# DM2097_Connector_A.net
KiCad netlist of a schematic drawn in Altium Designer
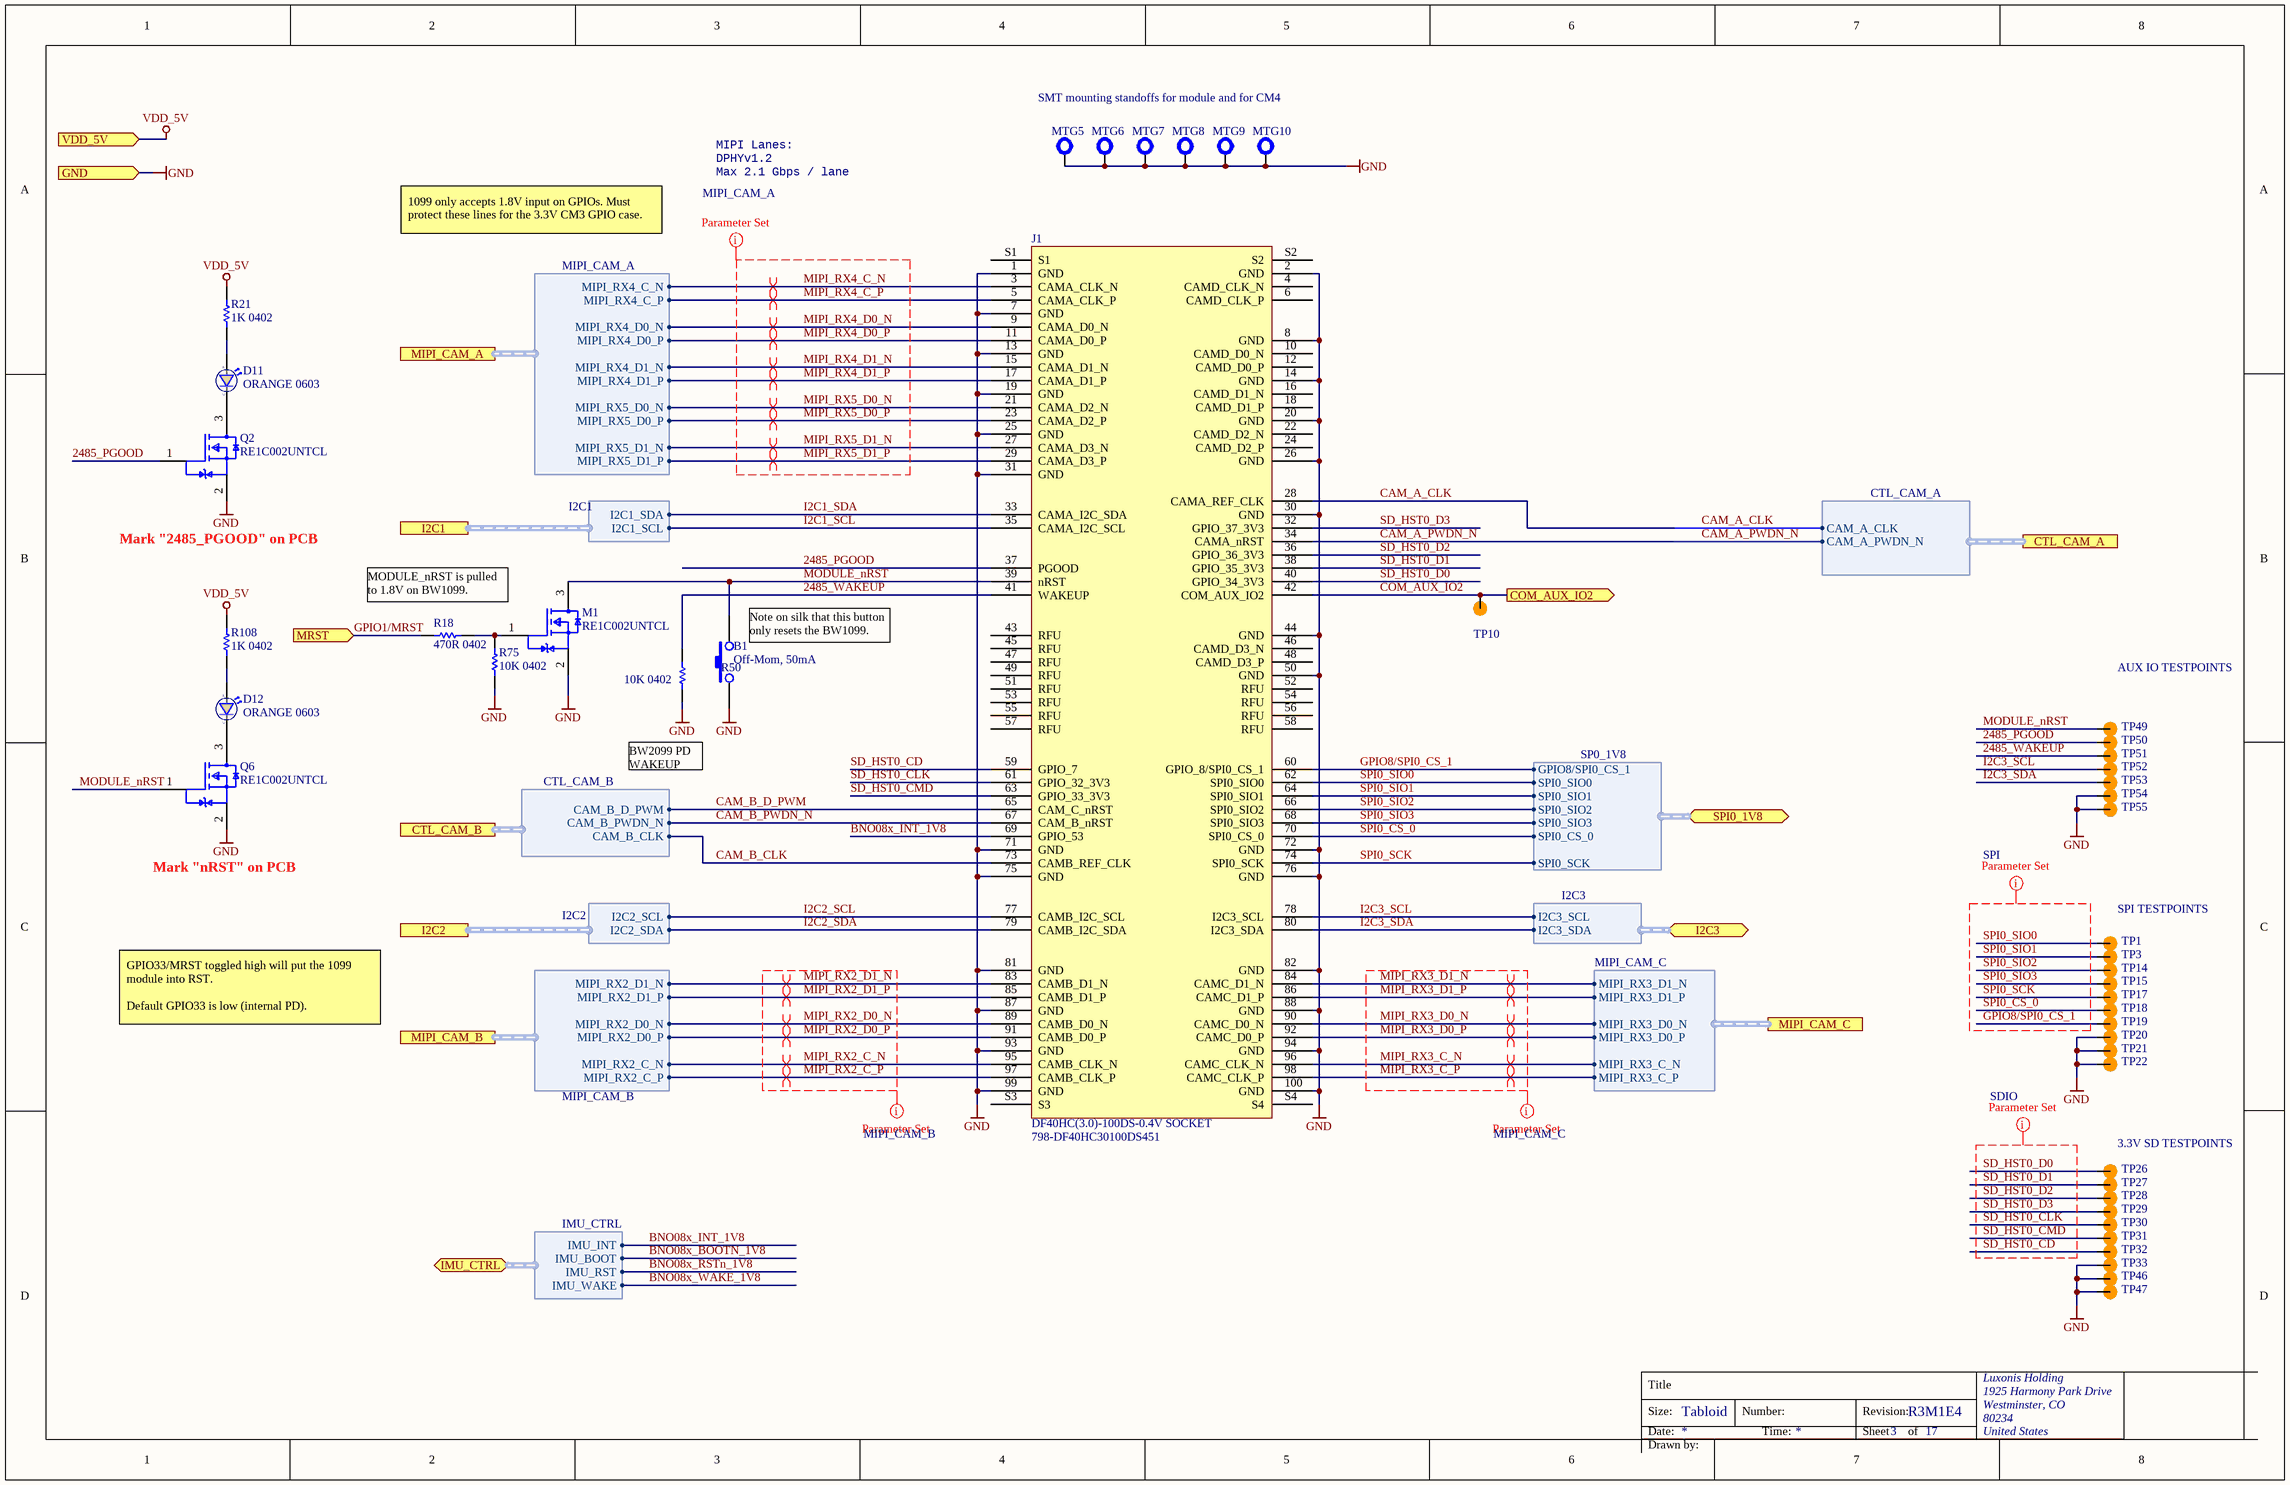
[diagram p0: DM2097_Connector_A.SchDoc]

(export (version "E")
  (design (tool "Eeschema 10.0.6"))
  (components
    (comp (ref "B1")
      (value "Off-Mom, 50mA")
      (footprint "LuxonisMaster:DTSM-32N-V")
      (description "SWITCH TACTILE SMT 3.5mm * 6mm , brown 160gf")
      (libsource (lib "LuxonisMaster") (part "DTSM-32N-V"))
    )
    (comp (ref "D11")
      (value "ORANGE 0603")
      (footprint "LuxonisMaster:SML_D1xx8W")
      (description "LED ORANGE DIFFUSED 0603 SMD Orange 605nm LED Indication - Discrete 2.2V 0603 (1608 Metric)")
      (libsource (lib "LuxonisMaster") (part "SML-D12D8WT86"))
    )
    (comp (ref "D12")
      (value "ORANGE 0603")
      (footprint "LuxonisMaster:SML_D1xx8W")
      (description "LED ORANGE DIFFUSED 0603 SMD Orange 605nm LED Indication - Discrete 2.2V 0603 (1608 Metric)")
      (libsource (lib "LuxonisMaster") (part "SML-D12D8WT86"))
    )
    (comp (ref "J1")
      (value "DF40HC(3.0)-100DS-0.4V SOCKET")
      (footprint "DF40HC-3.0-100DS-0.4V_minpad")
      (description "Conn Board to Board RCP 100 POS 0.4mm Solder ST SMD T/R")
      (fields (field (name "SUPPLIER PART NUMBER 1") "798-DF40HC30100DS451"))
      (libsource (lib "LuxonisMaster_OPAL") (part "BW2099_SCKT_Conn_A"))
    )
    (comp (ref "M1")
      (value "RE1C002UNTCL")
      (footprint "LuxonisMaster:RE1C002UNTCL")
      (description "VISHAY - SI1062X-T1-GE3 - MOSFET Transistor, N Channel, 530 mA, 20 V, 0.35 ohm, 4.5 V, 1 V")
      (libsource (lib "LuxonisMaster") (part "RE1C002UNTCL"))
    )
    (comp (ref "MTG5")
      (value "M2, 3MM steel spacer on M2.5 mounting pad")
      (footprint "9774030943R")
      (description "Spacers/Standoffs")
      (libsource (lib "DM1097_R1M1E1") (part "9774030943R"))
    )
    (comp (ref "MTG6")
      (value "M2, 3MM steel spacer on M2.5 mounting pad")
      (footprint "9774030943R")
      (description "Spacers/Standoffs")
      (libsource (lib "DM1097_R1M1E1") (part "9774030943R"))
    )
    (comp (ref "MTG7")
      (value "M2, 3MM steel spacer on M2.5 mounting pad")
      (footprint "9774030943R")
      (description "Spacers/Standoffs")
      (libsource (lib "DM1097_R1M1E1") (part "9774030943R"))
    )
    (comp (ref "MTG8")
      (value "M2, 3MM steel spacer on M2.5 mounting pad")
      (footprint "9774030943R")
      (description "Spacers/Standoffs")
      (libsource (lib "DM1097_R1M1E1") (part "9774030943R"))
    )
    (comp (ref "MTG9")
      (value "M2, 3MM steel spacer on M2.5 mounting pad")
      (footprint "9774030943R")
      (description "Spacers/Standoffs")
      (libsource (lib "DM1097_R1M1E1") (part "9774030943R"))
    )
    (comp (ref "MTG10")
      (value "M2, 3MM steel spacer on M2.5 mounting pad")
      (footprint "9774030943R")
      (description "Spacers/Standoffs")
      (libsource (lib "DM1097_R1M1E1") (part "9774030943R"))
    )
    (comp (ref "Q2")
      (value "RE1C002UNTCL")
      (footprint "LuxonisMaster:RE1C002UNTCL")
      (description "VISHAY - SI1062X-T1-GE3 - MOSFET Transistor, N Channel, 530 mA, 20 V, 0.35 ohm, 4.5 V, 1 V")
      (libsource (lib "LuxonisMaster") (part "RE1C002UNTCL"))
    )
    (comp (ref "Q6")
      (value "RE1C002UNTCL")
      (footprint "LuxonisMaster:RE1C002UNTCL")
      (description "VISHAY - SI1062X-T1-GE3 - MOSFET Transistor, N Channel, 530 mA, 20 V, 0.35 ohm, 4.5 V, 1 V")
      (libsource (lib "LuxonisMaster") (part "RE1C002UNTCL"))
    )
    (comp (ref "R18")
      (value "470R 0402")
      (footprint "RES_Altium_Vault_Generic:RESC0402(1005)_N")
      (description "RES SMD 470 OHM 1% 1/16W 0402")
      (fields (field (name "TOLERANCE") "1%"))
      (libsource (lib "LuxonisMaster") (part "CRCW0402470RFKED"))
    )
    (comp (ref "R21")
      (value "1K 0402")
      (footprint "RES_Altium_Vault_Generic:RESC0402(1005)_L")
      (fields (field (name "TOLERANCE") "1%"))
      (libsource (lib "LuxonisMaster") (part "RC0402FR-071KL"))
    )
    (comp (ref "R50")
      (value "10K 0402")
      (footprint "RES_Altium_Vault_Generic:RESC0402(1005)_L")
      (fields (field (name "TOLERANCE") "1%"))
      (libsource (lib "LuxonisMaster") (part "RC0402FR-1310KL"))
    )
    (comp (ref "R75")
      (value "10K 0402")
      (footprint "RES_Altium_Vault_Generic:RESC0402(1005)_N")
      (fields (field (name "TOLERANCE") "1%"))
      (libsource (lib "LuxonisMaster") (part "RC0402FR-1310KL"))
    )
    (comp (ref "R108")
      (value "1K 0402")
      (footprint "RES_Altium_Vault_Generic:RESC0402(1005)_L")
      (fields (field (name "TOLERANCE") "1%"))
      (libsource (lib "LuxonisMaster") (part "RC0402FR-071KL"))
    )
    (comp (ref "TP1")
      (value "TP100_200_NS")
      (footprint "LuxonisMaster:TP100_200_NS")
      (libsource (lib "LuxonisMaster") (part "TEST_POINT"))
    )
    (comp (ref "TP3")
      (value "TP100_200_NS")
      (footprint "LuxonisMaster:TP100_200_NS")
      (libsource (lib "LuxonisMaster") (part "TEST_POINT"))
    )
    (comp (ref "TP10")
      (value "TP100_200_NS")
      (footprint "LuxonisMaster:TP100_200_NS")
      (libsource (lib "LuxonisMaster") (part "TEST_POINT"))
    )
    (comp (ref "TP14")
      (value "TP100_200_NS")
      (footprint "LuxonisMaster:TP100_200_NS")
      (libsource (lib "LuxonisMaster") (part "TEST_POINT"))
    )
    (comp (ref "TP15")
      (value "TP100_200_NS")
      (footprint "LuxonisMaster:TP100_200_NS")
      (libsource (lib "LuxonisMaster") (part "TEST_POINT"))
    )
    (comp (ref "TP17")
      (value "TP100_200_NS")
      (footprint "LuxonisMaster:TP100_200_NS")
      (libsource (lib "LuxonisMaster") (part "TEST_POINT"))
    )
    (comp (ref "TP18")
      (value "TP100_200_NS")
      (footprint "LuxonisMaster:TP100_200_NS")
      (libsource (lib "LuxonisMaster") (part "TEST_POINT"))
    )
    (comp (ref "TP19")
      (value "TP100_200_NS")
      (footprint "LuxonisMaster:TP100_200_NS")
      (libsource (lib "LuxonisMaster") (part "TEST_POINT"))
    )
    (comp (ref "TP20")
      (value "TP100_200_NS")
      (footprint "LuxonisMaster:TP100_200_NS")
      (libsource (lib "LuxonisMaster") (part "TEST_POINT"))
    )
    (comp (ref "TP21")
      (value "TP100_200_NS")
      (footprint "LuxonisMaster:TP100_200_NS")
      (libsource (lib "LuxonisMaster") (part "TEST_POINT"))
    )
    (comp (ref "TP22")
      (value "TP100_200_NS")
      (footprint "LuxonisMaster:TP100_200_NS")
      (libsource (lib "LuxonisMaster") (part "TEST_POINT"))
    )
    (comp (ref "TP26")
      (value "TP100_200_NS")
      (footprint "LuxonisMaster:TP100_200_NS")
      (libsource (lib "LuxonisMaster") (part "TEST_POINT"))
    )
    (comp (ref "TP27")
      (value "TP100_200_NS")
      (footprint "LuxonisMaster:TP100_200_NS")
      (libsource (lib "LuxonisMaster") (part "TEST_POINT"))
    )
    (comp (ref "TP28")
      (value "TP100_200_NS")
      (footprint "LuxonisMaster:TP100_200_NS")
      (libsource (lib "LuxonisMaster") (part "TEST_POINT"))
    )
    (comp (ref "TP29")
      (value "TP100_200_NS")
      (footprint "LuxonisMaster:TP100_200_NS")
      (libsource (lib "LuxonisMaster") (part "TEST_POINT"))
    )
    (comp (ref "TP30")
      (value "TP100_200_NS")
      (footprint "LuxonisMaster:TP100_200_NS")
      (libsource (lib "LuxonisMaster") (part "TEST_POINT"))
    )
    (comp (ref "TP31")
      (value "TP100_200_NS")
      (footprint "LuxonisMaster:TP100_200_NS")
      (libsource (lib "LuxonisMaster") (part "TEST_POINT"))
    )
    (comp (ref "TP32")
      (value "TP100_200_NS")
      (footprint "LuxonisMaster:TP100_200_NS")
      (libsource (lib "LuxonisMaster") (part "TEST_POINT"))
    )
    (comp (ref "TP33")
      (value "TP100_200_NS")
      (footprint "LuxonisMaster:TP100_200_NS")
      (libsource (lib "LuxonisMaster") (part "TEST_POINT"))
    )
    (comp (ref "TP46")
      (value "TP100_200_NS")
      (footprint "LuxonisMaster:TP100_200_NS")
      (libsource (lib "LuxonisMaster") (part "TEST_POINT"))
    )
    (comp (ref "TP47")
      (value "TP100_200_NS")
      (footprint "LuxonisMaster:TP100_200_NS")
      (libsource (lib "LuxonisMaster") (part "TEST_POINT"))
    )
    (comp (ref "TP49")
      (value "TP100_200_NS")
      (footprint "LuxonisMaster:TP100_200_NS")
      (libsource (lib "LuxonisMaster") (part "TEST_POINT"))
    )
    (comp (ref "TP50")
      (value "TP100_200_NS")
      (footprint "LuxonisMaster:TP100_200_NS")
      (libsource (lib "LuxonisMaster") (part "TEST_POINT"))
    )
    (comp (ref "TP51")
      (value "TP100_200_NS")
      (footprint "LuxonisMaster:TP100_200_NS")
      (libsource (lib "LuxonisMaster") (part "TEST_POINT"))
    )
    (comp (ref "TP52")
      (value "TP100_200_NS")
      (footprint "LuxonisMaster:TP100_200_NS")
      (libsource (lib "LuxonisMaster") (part "TEST_POINT"))
    )
    (comp (ref "TP53")
      (value "TP100_200_NS")
      (footprint "LuxonisMaster:TP100_200_NS")
      (libsource (lib "LuxonisMaster") (part "TEST_POINT"))
    )
    (comp (ref "TP54")
      (value "TP100_200_NS")
      (footprint "LuxonisMaster:TP100_200_NS")
      (libsource (lib "LuxonisMaster") (part "TEST_POINT"))
    )
    (comp (ref "TP55")
      (value "TP100_200_NS")
      (footprint "LuxonisMaster:TP100_200_NS")
      (libsource (lib "LuxonisMaster") (part "TEST_POINT"))
    )
  )
  (nets
    (net (code "11") (name "/2485_PGOOD") (class "Default")
      (node (ref "J1") (pin "37") (pinfunction "PGOOD_37") (pintype "passive"))
      (node (ref "Q2") (pin "1") (pinfunction "Gate_1") (pintype "passive"))
      (node (ref "TP50") (pin "1") (pintype "passive"))
    )
    (net (code "12") (name "/2485_WAKEUP") (class "Default")
      (node (ref "J1") (pin "41") (pinfunction "WAKEUP_41") (pintype "passive"))
      (node (ref "R50") (pin "2") (pinfunction "2_2") (pintype "passive"))
      (node (ref "TP51") (pin "1") (pintype "passive"))
    )
    (net (code "14") (name "/BNO08x_INT_1V8") (class "Default")
      (node (ref "J1") (pin "69") (pinfunction "GPIO_53_69") (pintype "passive"))
    )
    (net (code "17") (name "/CAM_A_CLK") (class "Default")
      (node (ref "J1") (pin "28") (pinfunction "CAMA_REF_CLK_28") (pintype "passive"))
    )
    (net (code "18") (name "/CAM_A_PWDN_N") (class "Default")
      (node (ref "J1") (pin "34") (pinfunction "CAMA_nRST_34") (pintype "passive"))
    )
    (net (code "19") (name "/CAM_B_CLK") (class "Default")
      (node (ref "J1") (pin "73") (pinfunction "CAMB_REF_CLK_73") (pintype "passive"))
    )
    (net (code "20") (name "/CAM_B_D_PWM") (class "Default")
      (node (ref "J1") (pin "65") (pinfunction "CAM_C_nRST_65") (pintype "passive"))
    )
    (net (code "21") (name "/CAM_B_PWDN_N") (class "Default")
      (node (ref "J1") (pin "67") (pinfunction "CAM_B_nRST_67") (pintype "passive"))
    )
    (net (code "22") (name "/COM_AUX_IO2") (class "Default")
      (node (ref "J1") (pin "42") (pinfunction "COM_AUX_IO2_42") (pintype "passive"))
      (node (ref "TP10") (pin "1") (pintype "passive"))
    )
    (net (code "23") (name "/GPIO1{slash}MRST") (class "Default")
      (node (ref "R18") (pin "1") (pinfunction "1_1") (pintype "passive"))
    )
    (net (code "24") (name "/GPIO8{slash}SPI0_CS_1") (class "Default")
      (node (ref "J1") (pin "60") (pinfunction "GPIO_8/SPI0_CS_1_60") (pintype "passive"))
      (node (ref "TP19") (pin "1") (pintype "passive"))
    )
    (net (code "25") (name "/I2C1_SCL") (class "Default")
      (node (ref "J1") (pin "35") (pinfunction "CAMA_I2C_SCL_35") (pintype "passive"))
    )
    (net (code "26") (name "/I2C1_SDA") (class "Default")
      (node (ref "J1") (pin "33") (pinfunction "CAMA_I2C_SDA_33") (pintype "passive"))
    )
    (net (code "27") (name "/I2C2_SCL") (class "Default")
      (node (ref "J1") (pin "77") (pinfunction "CAMB_I2C_SCL_77") (pintype "passive"))
    )
    (net (code "28") (name "/I2C2_SDA") (class "Default")
      (node (ref "J1") (pin "79") (pinfunction "CAMB_I2C_SDA_79") (pintype "passive"))
    )
    (net (code "29") (name "/I2C3_SCL") (class "Default")
      (node (ref "J1") (pin "78") (pinfunction "I2C3_SCL_78") (pintype "passive"))
      (node (ref "TP52") (pin "1") (pintype "passive"))
    )
    (net (code "30") (name "/I2C3_SDA") (class "Default")
      (node (ref "J1") (pin "80") (pinfunction "I2C3_SDA_80") (pintype "passive"))
      (node (ref "TP53") (pin "1") (pintype "passive"))
    )
    (net (code "31") (name "/MIPI_RX2_C_N") (class "Default")
      (node (ref "J1") (pin "95") (pinfunction "CAMB_CLK_N_95") (pintype "passive"))
    )
    (net (code "32") (name "/MIPI_RX2_C_P") (class "Default")
      (node (ref "J1") (pin "97") (pinfunction "CAMB_CLK_P_97") (pintype "passive"))
    )
    (net (code "33") (name "/MIPI_RX2_D0_N") (class "Default")
      (node (ref "J1") (pin "89") (pinfunction "CAMB_D0_N_89") (pintype "passive"))
    )
    (net (code "34") (name "/MIPI_RX2_D0_P") (class "Default")
      (node (ref "J1") (pin "91") (pinfunction "CAMB_D0_P_91") (pintype "passive"))
    )
    (net (code "35") (name "/MIPI_RX2_D1_N") (class "Default")
      (node (ref "J1") (pin "83") (pinfunction "CAMB_D1_N_83") (pintype "passive"))
    )
    (net (code "36") (name "/MIPI_RX2_D1_P") (class "Default")
      (node (ref "J1") (pin "85") (pinfunction "CAMB_D1_P_85") (pintype "passive"))
    )
    (net (code "37") (name "/MIPI_RX3_C_N") (class "Default")
      (node (ref "J1") (pin "96") (pinfunction "CAMC_CLK_N_96") (pintype "passive"))
    )
    (net (code "38") (name "/MIPI_RX3_C_P") (class "Default")
      (node (ref "J1") (pin "98") (pinfunction "CAMC_CLK_P_98") (pintype "passive"))
    )
    (net (code "39") (name "/MIPI_RX3_D0_N") (class "Default")
      (node (ref "J1") (pin "90") (pinfunction "CAMC_D0_N_90") (pintype "passive"))
    )
    (net (code "40") (name "/MIPI_RX3_D0_P") (class "Default")
      (node (ref "J1") (pin "92") (pinfunction "CAMC_D0_P_92") (pintype "passive"))
    )
    (net (code "41") (name "/MIPI_RX3_D1_N") (class "Default")
      (node (ref "J1") (pin "84") (pinfunction "CAMC_D1_N_84") (pintype "passive"))
    )
    (net (code "42") (name "/MIPI_RX3_D1_P") (class "Default")
      (node (ref "J1") (pin "86") (pinfunction "CAMC_D1_P_86") (pintype "passive"))
    )
    (net (code "43") (name "/MIPI_RX4_C_N") (class "Default")
      (node (ref "J1") (pin "3") (pinfunction "CAMA_CLK_N_3") (pintype "passive"))
    )
    (net (code "44") (name "/MIPI_RX4_C_P") (class "Default")
      (node (ref "J1") (pin "5") (pinfunction "CAMA_CLK_P_5") (pintype "passive"))
    )
    (net (code "45") (name "/MIPI_RX4_D0_N") (class "Default")
      (node (ref "J1") (pin "9") (pinfunction "CAMA_D0_N_9") (pintype "passive"))
    )
    (net (code "46") (name "/MIPI_RX4_D0_P") (class "Default")
      (node (ref "J1") (pin "11") (pinfunction "CAMA_D0_P_11") (pintype "passive"))
    )
    (net (code "47") (name "/MIPI_RX4_D1_N") (class "Default")
      (node (ref "J1") (pin "15") (pinfunction "CAMA_D1_N_15") (pintype "passive"))
    )
    (net (code "48") (name "/MIPI_RX4_D1_P") (class "Default")
      (node (ref "J1") (pin "17") (pinfunction "CAMA_D1_P_17") (pintype "passive"))
    )
    (net (code "49") (name "/MIPI_RX5_D0_N") (class "Default")
      (node (ref "J1") (pin "21") (pinfunction "CAMA_D2_N_21") (pintype "passive"))
    )
    (net (code "50") (name "/MIPI_RX5_D0_P") (class "Default")
      (node (ref "J1") (pin "23") (pinfunction "CAMA_D2_P_23") (pintype "passive"))
    )
    (net (code "51") (name "/MIPI_RX5_D1_N") (class "Default")
      (node (ref "J1") (pin "27") (pinfunction "CAMA_D3_N_27") (pintype "passive"))
    )
    (net (code "52") (name "/MIPI_RX5_D1_P") (class "Default")
      (node (ref "J1") (pin "29") (pinfunction "CAMA_D3_P_29") (pintype "passive"))
    )
    (net (code "53") (name "/MODULE_nRST") (class "Default")
      (node (ref "B1") (pin "2") (pinfunction "2_2") (pintype "passive"))
      (node (ref "J1") (pin "39") (pinfunction "nRST_39") (pintype "passive"))
      (node (ref "M1") (pin "3") (pinfunction "Drain_3") (pintype "passive"))
      (node (ref "Q6") (pin "1") (pinfunction "Gate_1") (pintype "passive"))
      (node (ref "TP49") (pin "1") (pintype "passive"))
    )
    (net (code "54") (name "/SD_HST0_CD") (class "Default")
      (node (ref "J1") (pin "59") (pinfunction "GPIO_7_59") (pintype "passive"))
      (node (ref "TP32") (pin "1") (pintype "passive"))
    )
    (net (code "55") (name "/SD_HST0_CLK") (class "Default")
      (node (ref "J1") (pin "61") (pinfunction "GPIO_32_3V3_61") (pintype "passive"))
      (node (ref "TP30") (pin "1") (pintype "passive"))
    )
    (net (code "56") (name "/SD_HST0_CMD") (class "Default")
      (node (ref "J1") (pin "63") (pinfunction "GPIO_33_3V3_63") (pintype "passive"))
      (node (ref "TP31") (pin "1") (pintype "passive"))
    )
    (net (code "57") (name "/SD_HST0_D0") (class "Default")
      (node (ref "J1") (pin "40") (pinfunction "GPIO_34_3V3_40") (pintype "passive"))
      (node (ref "TP26") (pin "1") (pintype "passive"))
    )
    (net (code "58") (name "/SD_HST0_D1") (class "Default")
      (node (ref "J1") (pin "38") (pinfunction "GPIO_35_3V3_38") (pintype "passive"))
      (node (ref "TP27") (pin "1") (pintype "passive"))
    )
    (net (code "59") (name "/SD_HST0_D2") (class "Default")
      (node (ref "J1") (pin "36") (pinfunction "GPIO_36_3V3_36") (pintype "passive"))
      (node (ref "TP28") (pin "1") (pintype "passive"))
    )
    (net (code "60") (name "/SD_HST0_D3") (class "Default")
      (node (ref "J1") (pin "32") (pinfunction "GPIO_37_3V3_32") (pintype "passive"))
      (node (ref "TP29") (pin "1") (pintype "passive"))
    )
    (net (code "61") (name "/SPI0_CS_0") (class "Default")
      (node (ref "J1") (pin "70") (pinfunction "SPI0_CS_0_70") (pintype "passive"))
      (node (ref "TP18") (pin "1") (pintype "passive"))
    )
    (net (code "62") (name "/SPI0_SCK") (class "Default")
      (node (ref "J1") (pin "74") (pinfunction "SPI0_SCK_74") (pintype "passive"))
      (node (ref "TP17") (pin "1") (pintype "passive"))
    )
    (net (code "63") (name "/SPI0_SIO0") (class "Default")
      (node (ref "J1") (pin "62") (pinfunction "SPI0_SIO0_62") (pintype "passive"))
      (node (ref "TP1") (pin "1") (pintype "passive"))
    )
    (net (code "64") (name "/SPI0_SIO1") (class "Default")
      (node (ref "J1") (pin "64") (pinfunction "SPI0_SIO1_64") (pintype "passive"))
      (node (ref "TP3") (pin "1") (pintype "passive"))
    )
    (net (code "65") (name "/SPI0_SIO2") (class "Default")
      (node (ref "J1") (pin "66") (pinfunction "SPI0_SIO2_66") (pintype "passive"))
      (node (ref "TP14") (pin "1") (pintype "passive"))
    )
    (net (code "66") (name "/SPI0_SIO3") (class "Default")
      (node (ref "J1") (pin "68") (pinfunction "SPI0_SIO3_68") (pintype "passive"))
      (node (ref "TP15") (pin "1") (pintype "passive"))
    )
    (net (code "77") (name "GND") (class "Default")
      (node (ref "B1") (pin "1") (pinfunction "1_1") (pintype "passive"))
      (node (ref "J1") (pin "1") (pinfunction "GND_1") (pintype "passive"))
      (node (ref "J1") (pin "100") (pinfunction "GND_100") (pintype "passive"))
      (node (ref "J1") (pin "13") (pinfunction "GND_13") (pintype "passive"))
      (node (ref "J1") (pin "14") (pinfunction "GND_14") (pintype "passive"))
      (node (ref "J1") (pin "19") (pinfunction "GND_19") (pintype "passive"))
      (node (ref "J1") (pin "2") (pinfunction "GND_2") (pintype "passive"))
      (node (ref "J1") (pin "20") (pinfunction "GND_20") (pintype "passive"))
      (node (ref "J1") (pin "25") (pinfunction "GND_25") (pintype "passive"))
      (node (ref "J1") (pin "26") (pinfunction "GND_26") (pintype "passive"))
      (node (ref "J1") (pin "30") (pinfunction "GND_30") (pintype "passive"))
      (node (ref "J1") (pin "31") (pinfunction "GND_31") (pintype "passive"))
      (node (ref "J1") (pin "44") (pinfunction "GND_44") (pintype "passive"))
      (node (ref "J1") (pin "50") (pinfunction "GND_50") (pintype "passive"))
      (node (ref "J1") (pin "7") (pinfunction "GND_7") (pintype "passive"))
      (node (ref "J1") (pin "71") (pinfunction "GND_71") (pintype "passive"))
      (node (ref "J1") (pin "72") (pinfunction "GND_72") (pintype "passive"))
      (node (ref "J1") (pin "75") (pinfunction "GND_75") (pintype "passive"))
      (node (ref "J1") (pin "76") (pinfunction "GND_76") (pintype "passive"))
      (node (ref "J1") (pin "8") (pinfunction "GND_8") (pintype "passive"))
      (node (ref "J1") (pin "81") (pinfunction "GND_81") (pintype "passive"))
      (node (ref "J1") (pin "82") (pinfunction "GND_82") (pintype "passive"))
      (node (ref "J1") (pin "87") (pinfunction "GND_87") (pintype "passive"))
      (node (ref "J1") (pin "88") (pinfunction "GND_88") (pintype "passive"))
      (node (ref "J1") (pin "93") (pinfunction "GND_93") (pintype "passive"))
      (node (ref "J1") (pin "94") (pinfunction "GND_94") (pintype "passive"))
      (node (ref "J1") (pin "99") (pinfunction "GND_99") (pintype "passive"))
      (node (ref "M1") (pin "2") (pinfunction "Source_2") (pintype "passive"))
      (node (ref "MTG10") (pin "1") (pintype "passive"))
      (node (ref "MTG5") (pin "1") (pintype "passive"))
      (node (ref "MTG6") (pin "1") (pintype "passive"))
      (node (ref "MTG7") (pin "1") (pintype "passive"))
      (node (ref "MTG8") (pin "1") (pintype "passive"))
      (node (ref "MTG9") (pin "1") (pintype "passive"))
      (node (ref "Q2") (pin "2") (pinfunction "Source_2") (pintype "passive"))
      (node (ref "Q6") (pin "2") (pinfunction "Source_2") (pintype "passive"))
      (node (ref "R50") (pin "1") (pinfunction "1_1") (pintype "passive"))
      (node (ref "R75") (pin "1") (pinfunction "1_1") (pintype "passive"))
      (node (ref "TP20") (pin "1") (pintype "passive"))
      (node (ref "TP21") (pin "1") (pintype "passive"))
      (node (ref "TP22") (pin "1") (pintype "passive"))
      (node (ref "TP33") (pin "1") (pintype "passive"))
      (node (ref "TP46") (pin "1") (pintype "passive"))
      (node (ref "TP47") (pin "1") (pintype "passive"))
      (node (ref "TP54") (pin "1") (pintype "passive"))
      (node (ref "TP55") (pin "1") (pintype "passive"))
    )
    (net (code "78") (name "Net-(D11-A)") (class "Default")
      (node (ref "D11") (pin "2") (pinfunction "A_2") (pintype "passive"))
      (node (ref "R21") (pin "1") (pinfunction "1_1") (pintype "passive"))
    )
    (net (code "79") (name "Net-(D11-C)") (class "Default")
      (node (ref "D11") (pin "1") (pinfunction "C_1") (pintype "passive"))
      (node (ref "Q2") (pin "3") (pinfunction "Drain_3") (pintype "passive"))
    )
    (net (code "80") (name "Net-(D12-A)") (class "Default")
      (node (ref "D12") (pin "2") (pinfunction "A_2") (pintype "passive"))
      (node (ref "R108") (pin "1") (pinfunction "1_1") (pintype "passive"))
    )
    (net (code "81") (name "Net-(D12-C)") (class "Default")
      (node (ref "D12") (pin "1") (pinfunction "C_1") (pintype "passive"))
      (node (ref "Q6") (pin "3") (pinfunction "Drain_3") (pintype "passive"))
    )
    (net (code "82") (name "Net-(M1-Gate)") (class "Default")
      (node (ref "M1") (pin "1") (pinfunction "Gate_1") (pintype "passive"))
      (node (ref "R18") (pin "2") (pinfunction "2_2") (pintype "passive"))
      (node (ref "R75") (pin "2") (pinfunction "2_2") (pintype "passive"))
    )
    (net (code "83") (name "VDD_5V") (class "Default")
      (node (ref "R108") (pin "2") (pinfunction "2_2") (pintype "passive"))
      (node (ref "R21") (pin "2") (pinfunction "2_2") (pintype "passive"))
    )
    (net (code "84") (name "unconnected-(J1-CAMD_CLK_N-Pad4)") (class "Default")
      (node (ref "J1") (pin "4") (pinfunction "CAMD_CLK_N_4") (pintype "passive"))
    )
    (net (code "85") (name "unconnected-(J1-CAMD_CLK_P-Pad6)") (class "Default")
      (node (ref "J1") (pin "6") (pinfunction "CAMD_CLK_P_6") (pintype "passive"))
    )
    (net (code "86") (name "unconnected-(J1-CAMD_D0_N-Pad10)") (class "Default")
      (node (ref "J1") (pin "10") (pinfunction "CAMD_D0_N_10") (pintype "passive"))
    )
    (net (code "87") (name "unconnected-(J1-CAMD_D0_P-Pad12)") (class "Default")
      (node (ref "J1") (pin "12") (pinfunction "CAMD_D0_P_12") (pintype "passive"))
    )
    (net (code "88") (name "unconnected-(J1-CAMD_D1_N-Pad16)") (class "Default")
      (node (ref "J1") (pin "16") (pinfunction "CAMD_D1_N_16") (pintype "passive"))
    )
    (net (code "89") (name "unconnected-(J1-CAMD_D1_P-Pad18)") (class "Default")
      (node (ref "J1") (pin "18") (pinfunction "CAMD_D1_P_18") (pintype "passive"))
    )
    (net (code "90") (name "unconnected-(J1-CAMD_D2_N-Pad22)") (class "Default")
      (node (ref "J1") (pin "22") (pinfunction "CAMD_D2_N_22") (pintype "passive"))
    )
    (net (code "91") (name "unconnected-(J1-CAMD_D2_P-Pad24)") (class "Default")
      (node (ref "J1") (pin "24") (pinfunction "CAMD_D2_P_24") (pintype "passive"))
    )
    (net (code "92") (name "unconnected-(J1-CAMD_D3_N-Pad46)") (class "Default")
      (node (ref "J1") (pin "46") (pinfunction "CAMD_D3_N_46") (pintype "passive"))
    )
    (net (code "93") (name "unconnected-(J1-CAMD_D3_P-Pad48)") (class "Default")
      (node (ref "J1") (pin "48") (pinfunction "CAMD_D3_P_48") (pintype "passive"))
    )
    (net (code "94") (name "unconnected-(J1-PadS1)") (class "Default")
      (node (ref "J1") (pin "S1") (pinfunction "S1_S1") (pintype "passive"))
    )
    (net (code "95") (name "unconnected-(J1-PadS2)") (class "Default")
      (node (ref "J1") (pin "S2") (pinfunction "S2_S2") (pintype "passive"))
    )
    (net (code "96") (name "unconnected-(J1-PadS3)") (class "Default")
      (node (ref "J1") (pin "S3") (pinfunction "S3_S3") (pintype "passive"))
    )
    (net (code "97") (name "unconnected-(J1-PadS4)") (class "Default")
      (node (ref "J1") (pin "S4") (pinfunction "S4_S4") (pintype "passive"))
    )
    (net (code "98") (name "unconnected-(J1-RFU-Pad43)") (class "Default")
      (node (ref "J1") (pin "43") (pinfunction "RFU_43") (pintype "passive"))
    )
    (net (code "99") (name "unconnected-(J1-RFU-Pad45)") (class "Default")
      (node (ref "J1") (pin "45") (pinfunction "RFU_45") (pintype "passive"))
    )
    (net (code "100") (name "unconnected-(J1-RFU-Pad47)") (class "Default")
      (node (ref "J1") (pin "47") (pinfunction "RFU_47") (pintype "passive"))
    )
    (net (code "101") (name "unconnected-(J1-RFU-Pad49)") (class "Default")
      (node (ref "J1") (pin "49") (pinfunction "RFU_49") (pintype "passive"))
    )
    (net (code "102") (name "unconnected-(J1-RFU-Pad51)") (class "Default")
      (node (ref "J1") (pin "51") (pinfunction "RFU_51") (pintype "passive"))
    )
    (net (code "103") (name "unconnected-(J1-RFU-Pad52)") (class "Default")
      (node (ref "J1") (pin "52") (pinfunction "RFU_52") (pintype "passive"))
    )
    (net (code "104") (name "unconnected-(J1-RFU-Pad53)") (class "Default")
      (node (ref "J1") (pin "53") (pinfunction "RFU_53") (pintype "passive"))
    )
    (net (code "105") (name "unconnected-(J1-RFU-Pad54)") (class "Default")
      (node (ref "J1") (pin "54") (pinfunction "RFU_54") (pintype "passive"))
    )
    (net (code "106") (name "unconnected-(J1-RFU-Pad55)") (class "Default")
      (node (ref "J1") (pin "55") (pinfunction "RFU_55") (pintype "passive"))
    )
    (net (code "107") (name "unconnected-(J1-RFU-Pad56)") (class "Default")
      (node (ref "J1") (pin "56") (pinfunction "RFU_56") (pintype "passive"))
    )
    (net (code "108") (name "unconnected-(J1-RFU-Pad57)") (class "Default")
      (node (ref "J1") (pin "57") (pinfunction "RFU_57") (pintype "passive"))
    )
    (net (code "109") (name "unconnected-(J1-RFU-Pad58)") (class "Default")
      (node (ref "J1") (pin "58") (pinfunction "RFU_58") (pintype "passive"))
    )
  )
)
